# Audio_Codec.net
KiCad netlist of a schematic drawn in Altium Designer
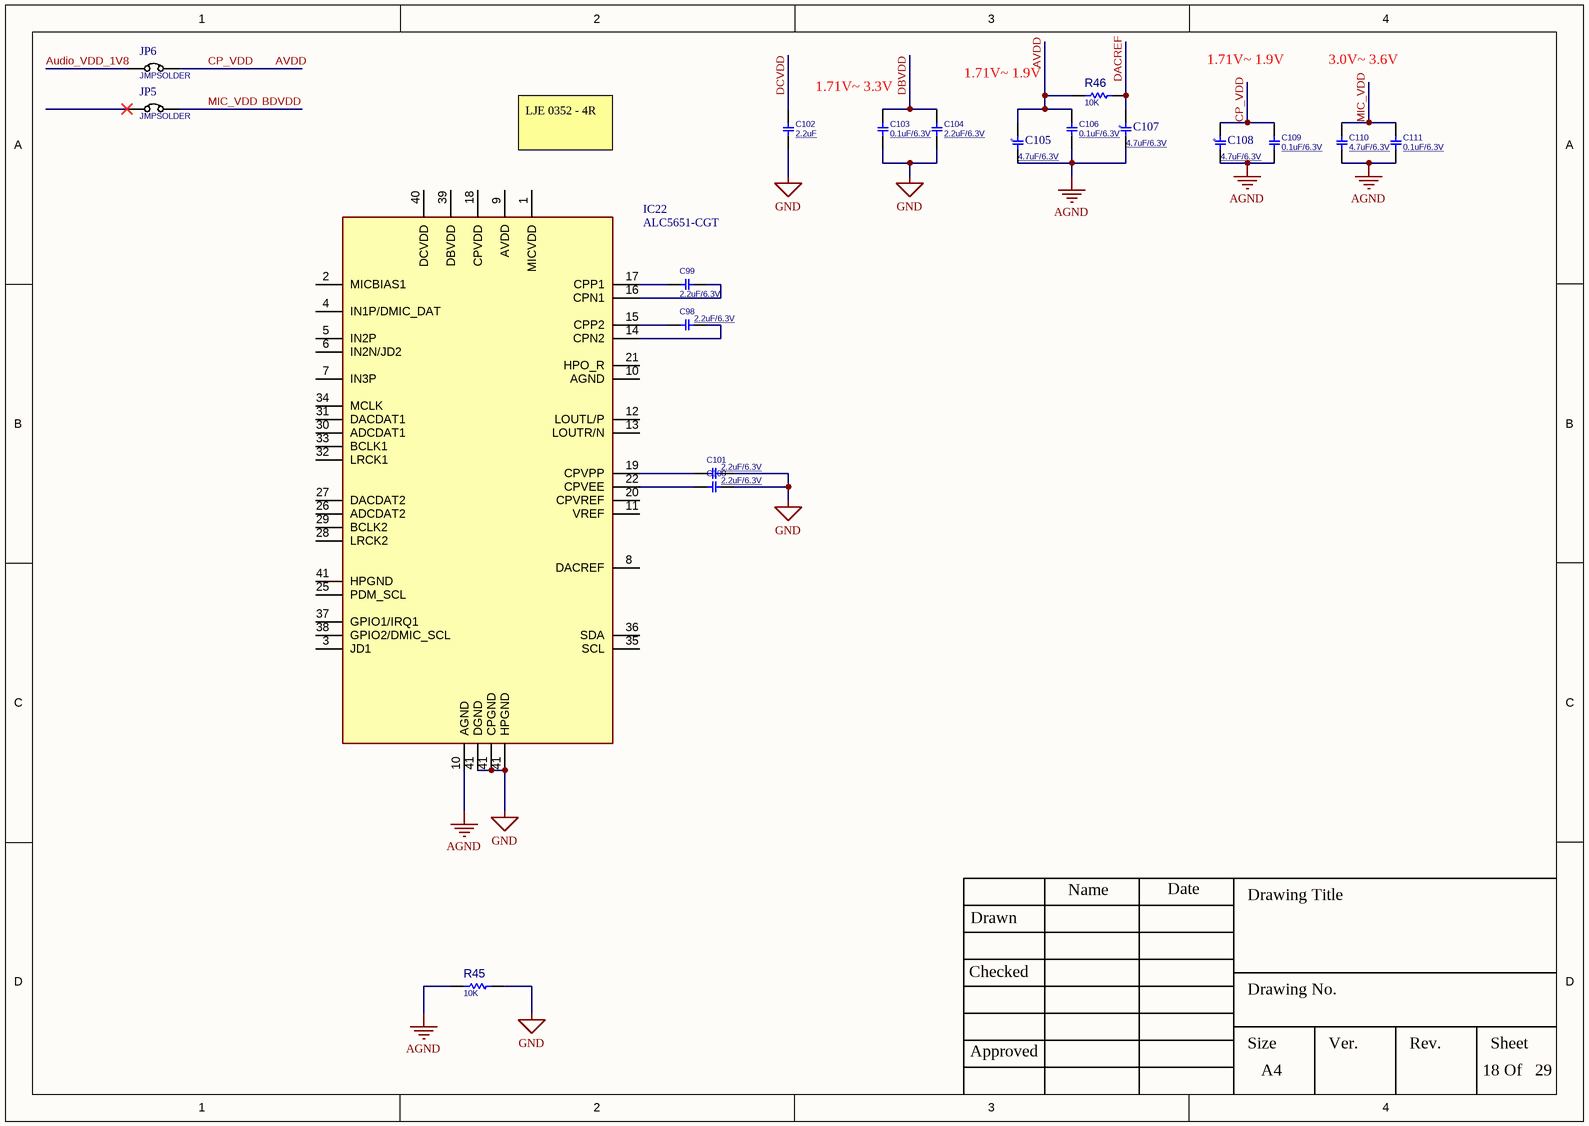
[diagram p0: Audio Codec.SchDoc]

(export (version "E")
  (design (tool "Eeschema 10.0.6"))
  (components
    (comp (ref "C98")
      (value "2.2uF/6.3V")
      (footprint "C0603")
      (description "CAP, MLCC, -F, -V, MATERIAL, -%, 0201")
      (fields (field (name "MANF_P#") "MANF_PART#"))
      (libsource (lib "passive_smd") (part "CAP_SMD_MLCC_0603"))
    )
    (comp (ref "C99")
      (value "2.2uF/6.3V")
      (footprint "C0603")
      (description "CAP, MLCC, -F, -V, MATERIAL, -%, 0201")
      (fields (field (name "MANF_P#") "MANF_PART#"))
      (libsource (lib "passive_smd") (part "CAP_SMD_MLCC_0603"))
    )
    (comp (ref "C100")
      (value "2.2uF/6.3V")
      (footprint "C0603")
      (description "CAP, MLCC, -F, -V, MATERIAL, -%, 0201")
      (fields (field (name "MANF_P#") "MANF_PART#"))
      (libsource (lib "passive_smd") (part "CAP_SMD_MLCC_0603"))
    )
    (comp (ref "C101")
      (value "2.2uF/6.3V")
      (footprint "C0603")
      (description "CAP, MLCC, -F, -V, MATERIAL, -%, 0201")
      (fields (field (name "MANF_P#") "MANF_PART#"))
      (libsource (lib "passive_smd") (part "CAP_SMD_MLCC_0603"))
    )
    (comp (ref "C102")
      (value "2.2uF")
      (footprint "C0603")
      (description "CAP, MLCC, -F, -V, MATERIAL, -%, 0201")
      (fields (field (name "MANF_P#") "MANF_PART#"))
      (libsource (lib "passive_smd") (part "CAP_SMD_MLCC_0603"))
    )
    (comp (ref "C103")
      (value "0.1uF/6.3V")
      (footprint "C0603")
      (description "CAP, MLCC, -F, -V, MATERIAL, -%, 0201")
      (fields (field (name "MANF_P#") "MANF_PART#"))
      (libsource (lib "passive_smd") (part "CAP_SMD_MLCC_0603"))
    )
    (comp (ref "C104")
      (value "2.2uF/6.3V")
      (footprint "C0603")
      (description "CAP, MLCC, -F, -V, MATERIAL, -%, 0201")
      (fields (field (name "MANF_P#") "MANF_PART#"))
      (libsource (lib "passive_smd") (part "CAP_SMD_MLCC_0603"))
    )
    (comp (ref "C105")
      (value "4.7uF/6.3V")
      (footprint "Cap_A")
      (description "Capacitor Tantalum SMD")
      (libsource (lib "Capacitor") (part "Capacitor Tantalum SMD"))
    )
    (comp (ref "C106")
      (value "0.1uF/6.3V")
      (footprint "C0603")
      (description "CAP, MLCC, -F, -V, MATERIAL, -%, 0201")
      (fields (field (name "MANF_P#") "MANF_PART#"))
      (libsource (lib "passive_smd") (part "CAP_SMD_MLCC_0603"))
    )
    (comp (ref "C107")
      (value "4.7uF/6.3V")
      (footprint "Cap_A")
      (description "Capacitor Tantalum SMD")
      (libsource (lib "Capacitor") (part "Capacitor Tantalum SMD"))
    )
    (comp (ref "C108")
      (value "4.7uF/6.3V")
      (footprint "Cap_A")
      (description "Capacitor Tantalum SMD")
      (libsource (lib "Capacitor") (part "Capacitor Tantalum SMD"))
    )
    (comp (ref "C109")
      (value "0.1uF/6.3V")
      (footprint "C0603")
      (description "CAP, MLCC, -F, -V, MATERIAL, -%, 0201")
      (fields (field (name "MANF_P#") "MANF_PART#"))
      (libsource (lib "passive_smd") (part "CAP_SMD_MLCC_0603"))
    )
    (comp (ref "C110")
      (value "4.7uF/6.3V")
      (footprint "C0805")
      (description "CAP, MLCC, -F, -V, MATERIAL, -%, 0201")
      (fields (field (name "MANF_P#") "MANF_PART#"))
      (libsource (lib "passive_smd") (part "CAP_SMD_MLCC_0805"))
    )
    (comp (ref "C111")
      (value "0.1uF/6.3V")
      (footprint "C0603")
      (description "CAP, MLCC, -F, -V, MATERIAL, -%, 0201")
      (fields (field (name "MANF_P#") "MANF_PART#"))
      (libsource (lib "passive_smd") (part "CAP_SMD_MLCC_0603"))
    )
    (comp (ref "IC22")
      (value "ALC5651-CGT")
      (footprint "SamacSys:QFN40P500X500X90-41N-D")
      (description "Integrated Circuit")
      (libsource (lib "SamacSys") (part "ALC5651-CGT"))
    )
    (comp (ref "JP5")
      (value "JMPSOLDER")
      (footprint "JP_40X50")
      (description "JUMPER, HEADER 2PIN")
      (fields (field (name "MANF") "MANF") (field (name "MANF_P#") "MANF_P#"))
      (libsource (lib "test-tp_jumper") (part "JUMPER_SOLDER"))
    )
    (comp (ref "JP6")
      (value "JMPSOLDER")
      (footprint "JP_40X50")
      (description "JUMPER, HEADER 2PIN")
      (fields (field (name "MANF") "MANF") (field (name "MANF_P#") "MANF_P#"))
      (libsource (lib "test-tp_jumper") (part "JUMPER_SOLDER"))
    )
    (comp (ref "R45")
      (value "10K")
      (footprint "R0603")
      (description "RESISTOR, SMD")
      (libsource (lib "passive_smd") (part "RES_SMD_0603"))
    )
    (comp (ref "R46")
      (value "10K")
      (footprint "R0603")
      (description "RESISTOR, SMD")
      (libsource (lib "passive_smd") (part "RES_SMD_0603"))
    )
  )
  (nets
    (net (code "1") (name "/AVDD") (class "Default")
      (node (ref "C105") (pin "2") (pinfunction "2_2") (pintype "passive"))
      (node (ref "C106") (pin "2") (pinfunction "2_2") (pintype "passive"))
      (node (ref "C108") (pin "2") (pinfunction "2_2") (pintype "passive"))
      (node (ref "C109") (pin "2") (pinfunction "2_2") (pintype "passive"))
      (node (ref "JP6") (pin "2") (pinfunction "2_2") (pintype "passive"))
      (node (ref "R46") (pin "1") (pinfunction "1_1") (pintype "passive"))
    )
    (net (code "2") (name "/Audio_VDD_1V8") (class "Default")
      (node (ref "JP6") (pin "1") (pinfunction "1_1") (pintype "passive"))
    )
    (net (code "3") (name "/BDVDD") (class "Default")
      (node (ref "C110") (pin "1") (pinfunction "1_1") (pintype "passive"))
      (node (ref "C111") (pin "1") (pinfunction "1_1") (pintype "passive"))
      (node (ref "JP5") (pin "2") (pinfunction "2_2") (pintype "passive"))
    )
    (net (code "4") (name "/DACREF") (class "Default")
      (node (ref "C107") (pin "2") (pinfunction "2_2") (pintype "passive"))
      (node (ref "R46") (pin "2") (pinfunction "2_2") (pintype "passive"))
    )
    (net (code "5") (name "/DBVDD") (class "Default")
      (node (ref "C103") (pin "2") (pinfunction "2_2") (pintype "passive"))
      (node (ref "C104") (pin "2") (pinfunction "2_2") (pintype "passive"))
    )
    (net (code "6") (name "/DCVDD") (class "Default")
      (node (ref "C102") (pin "2") (pinfunction "2_2") (pintype "passive"))
    )
    (net (code "7") (name "AGND") (class "Default")
      (node (ref "C105") (pin "1") (pinfunction "1_1") (pintype "passive"))
      (node (ref "C106") (pin "1") (pinfunction "1_1") (pintype "passive"))
      (node (ref "C107") (pin "1") (pinfunction "1_1") (pintype "passive"))
      (node (ref "C108") (pin "1") (pinfunction "1_1") (pintype "passive"))
      (node (ref "C109") (pin "1") (pinfunction "1_1") (pintype "passive"))
      (node (ref "C110") (pin "2") (pinfunction "2_2") (pintype "passive"))
      (node (ref "C111") (pin "2") (pinfunction "2_2") (pintype "passive"))
      (node (ref "IC22") (pin "10") (pinfunction "AGND_10") (pintype "passive"))
      (node (ref "R45") (pin "1") (pinfunction "1_1") (pintype "passive"))
    )
    (net (code "8") (name "GND") (class "Default")
      (node (ref "C100") (pin "1") (pinfunction "1_1") (pintype "passive"))
      (node (ref "C101") (pin "1") (pinfunction "1_1") (pintype "passive"))
      (node (ref "C102") (pin "1") (pinfunction "1_1") (pintype "passive"))
      (node (ref "C103") (pin "1") (pinfunction "1_1") (pintype "passive"))
      (node (ref "C104") (pin "1") (pinfunction "1_1") (pintype "passive"))
      (node (ref "IC22") (pin "41") (pinfunction "DGND_41") (pintype "passive"))
      (node (ref "R45") (pin "2") (pinfunction "2_2") (pintype "passive"))
    )
    (net (code "9") (name "Net-(IC22-CPN1)") (class "Default")
      (node (ref "C99") (pin "2") (pinfunction "2_2") (pintype "passive"))
      (node (ref "IC22") (pin "16") (pinfunction "CPN1_16") (pintype "passive"))
    )
    (net (code "10") (name "Net-(IC22-CPN2)") (class "Default")
      (node (ref "C98") (pin "1") (pinfunction "1_1") (pintype "passive"))
      (node (ref "IC22") (pin "14") (pinfunction "CPN2_14") (pintype "passive"))
    )
    (net (code "11") (name "Net-(IC22-CPP1)") (class "Default")
      (node (ref "C99") (pin "1") (pinfunction "1_1") (pintype "passive"))
      (node (ref "IC22") (pin "17") (pinfunction "CPP1_17") (pintype "passive"))
    )
    (net (code "12") (name "Net-(IC22-CPP2)") (class "Default")
      (node (ref "C98") (pin "2") (pinfunction "2_2") (pintype "passive"))
      (node (ref "IC22") (pin "15") (pinfunction "CPP2_15") (pintype "passive"))
    )
    (net (code "13") (name "Net-(IC22-CPVEE)") (class "Default")
      (node (ref "C100") (pin "2") (pinfunction "2_2") (pintype "passive"))
      (node (ref "IC22") (pin "22") (pinfunction "CPVEE_22") (pintype "passive"))
    )
    (net (code "14") (name "Net-(IC22-CPVPP)") (class "Default")
      (node (ref "C101") (pin "2") (pinfunction "2_2") (pintype "passive"))
      (node (ref "IC22") (pin "19") (pinfunction "CPVPP_19") (pintype "passive"))
    )
    (net (code "15") (name "unconnected-(IC22-ADCDAT1-Pad30)") (class "Default")
      (node (ref "IC22") (pin "30") (pinfunction "ADCDAT1_30") (pintype "passive"))
    )
    (net (code "16") (name "unconnected-(IC22-ADCDAT2-Pad26)") (class "Default")
      (node (ref "IC22") (pin "26") (pinfunction "ADCDAT2_26") (pintype "passive"))
    )
    (net (code "17") (name "unconnected-(IC22-AGND-Pad10)") (class "Default")
      (node (ref "IC22") (pin "10") (pinfunction "AGND_10") (pintype "passive"))
    )
    (net (code "18") (name "unconnected-(IC22-AVDD-Pad9)") (class "Default")
      (node (ref "IC22") (pin "9") (pinfunction "AVDD_9") (pintype "passive"))
    )
    (net (code "19") (name "unconnected-(IC22-BCLK1-Pad33)") (class "Default")
      (node (ref "IC22") (pin "33") (pinfunction "BCLK1_33") (pintype "passive"))
    )
    (net (code "20") (name "unconnected-(IC22-BCLK2-Pad29)") (class "Default")
      (node (ref "IC22") (pin "29") (pinfunction "BCLK2_29") (pintype "passive"))
    )
    (net (code "21") (name "unconnected-(IC22-CPVDD-Pad18)") (class "Default")
      (node (ref "IC22") (pin "18") (pinfunction "CPVDD_18") (pintype "passive"))
    )
    (net (code "22") (name "unconnected-(IC22-CPVREF-Pad20)") (class "Default")
      (node (ref "IC22") (pin "20") (pinfunction "CPVREF_20") (pintype "passive"))
    )
    (net (code "23") (name "unconnected-(IC22-DACDAT1-Pad31)") (class "Default")
      (node (ref "IC22") (pin "31") (pinfunction "DACDAT1_31") (pintype "passive"))
    )
    (net (code "24") (name "unconnected-(IC22-DACDAT2-Pad27)") (class "Default")
      (node (ref "IC22") (pin "27") (pinfunction "DACDAT2_27") (pintype "passive"))
    )
    (net (code "25") (name "unconnected-(IC22-DACREF-Pad8)") (class "Default")
      (node (ref "IC22") (pin "8") (pinfunction "DACREF_8") (pintype "passive"))
    )
    (net (code "26") (name "unconnected-(IC22-DBVDD-Pad39)") (class "Default")
      (node (ref "IC22") (pin "39") (pinfunction "DBVDD_39") (pintype "passive"))
    )
    (net (code "27") (name "unconnected-(IC22-DCVDD-Pad40)") (class "Default")
      (node (ref "IC22") (pin "40") (pinfunction "DCVDD_40") (pintype "passive"))
    )
    (net (code "28") (name "unconnected-(IC22-GPIO1{slash}IRQ1-Pad37)") (class "Default")
      (node (ref "IC22") (pin "37") (pinfunction "GPIO1/IRQ1_37") (pintype "passive"))
    )
    (net (code "29") (name "unconnected-(IC22-GPIO2{slash}DMIC_SCL-Pad38)") (class "Default")
      (node (ref "IC22") (pin "38") (pinfunction "GPIO2/DMIC_SCL_38") (pintype "passive"))
    )
    (net (code "30") (name "unconnected-(IC22-HPGND-Pad41)") (class "Default")
      (node (ref "IC22") (pin "41") (pinfunction "HPGND_41") (pintype "passive"))
    )
    (net (code "31") (name "unconnected-(IC22-HPO_R-Pad21)") (class "Default")
      (node (ref "IC22") (pin "21") (pinfunction "HPO_R_21") (pintype "passive"))
    )
    (net (code "32") (name "unconnected-(IC22-IN1P{slash}DMIC_DAT-Pad4)") (class "Default")
      (node (ref "IC22") (pin "4") (pinfunction "IN1P/DMIC_DAT_4") (pintype "passive"))
    )
    (net (code "33") (name "unconnected-(IC22-IN2N{slash}JD2-Pad6)") (class "Default")
      (node (ref "IC22") (pin "6") (pinfunction "IN2N/JD2_6") (pintype "passive"))
    )
    (net (code "34") (name "unconnected-(IC22-IN2P-Pad5)") (class "Default")
      (node (ref "IC22") (pin "5") (pinfunction "IN2P_5") (pintype "passive"))
    )
    (net (code "35") (name "unconnected-(IC22-IN3P-Pad7)") (class "Default")
      (node (ref "IC22") (pin "7") (pinfunction "IN3P_7") (pintype "passive"))
    )
    (net (code "36") (name "unconnected-(IC22-JD1-Pad3)") (class "Default")
      (node (ref "IC22") (pin "3") (pinfunction "JD1_3") (pintype "passive"))
    )
    (net (code "37") (name "unconnected-(IC22-LOUTL{slash}P-Pad12)") (class "Default")
      (node (ref "IC22") (pin "12") (pinfunction "LOUTL/P_12") (pintype "passive"))
    )
    (net (code "38") (name "unconnected-(IC22-LOUTR{slash}N-Pad13)") (class "Default")
      (node (ref "IC22") (pin "13") (pinfunction "LOUTR/N_13") (pintype "passive"))
    )
    (net (code "39") (name "unconnected-(IC22-LRCK1-Pad32)") (class "Default")
      (node (ref "IC22") (pin "32") (pinfunction "LRCK1_32") (pintype "passive"))
    )
    (net (code "40") (name "unconnected-(IC22-LRCK2-Pad28)") (class "Default")
      (node (ref "IC22") (pin "28") (pinfunction "LRCK2_28") (pintype "passive"))
    )
    (net (code "41") (name "unconnected-(IC22-MCLK-Pad34)") (class "Default")
      (node (ref "IC22") (pin "34") (pinfunction "MCLK_34") (pintype "passive"))
    )
    (net (code "42") (name "unconnected-(IC22-MICBIAS1-Pad2)") (class "Default")
      (node (ref "IC22") (pin "2") (pinfunction "MICBIAS1_2") (pintype "passive"))
    )
    (net (code "43") (name "unconnected-(IC22-MICVDD-Pad1)") (class "Default")
      (node (ref "IC22") (pin "1") (pinfunction "MICVDD_1") (pintype "passive"))
    )
    (net (code "44") (name "unconnected-(IC22-PDM_SCL-Pad25)") (class "Default")
      (node (ref "IC22") (pin "25") (pinfunction "PDM_SCL_25") (pintype "passive"))
    )
    (net (code "45") (name "unconnected-(IC22-SCL-Pad35)") (class "Default")
      (node (ref "IC22") (pin "35") (pinfunction "SCL_35") (pintype "passive"))
    )
    (net (code "46") (name "unconnected-(IC22-SDA-Pad36)") (class "Default")
      (node (ref "IC22") (pin "36") (pinfunction "SDA_36") (pintype "passive"))
    )
    (net (code "47") (name "unconnected-(IC22-VREF-Pad11)") (class "Default")
      (node (ref "IC22") (pin "11") (pinfunction "VREF_11") (pintype "passive"))
    )
    (net (code "48") (name "unconnected-(JP5-Pad1)") (class "Default")
      (node (ref "JP5") (pin "1") (pinfunction "1_1") (pintype "passive+no_connect"))
    )
  )
)
